# HyperArmBoard.net
KiCad netlist of a schematic drawn in EAGLE
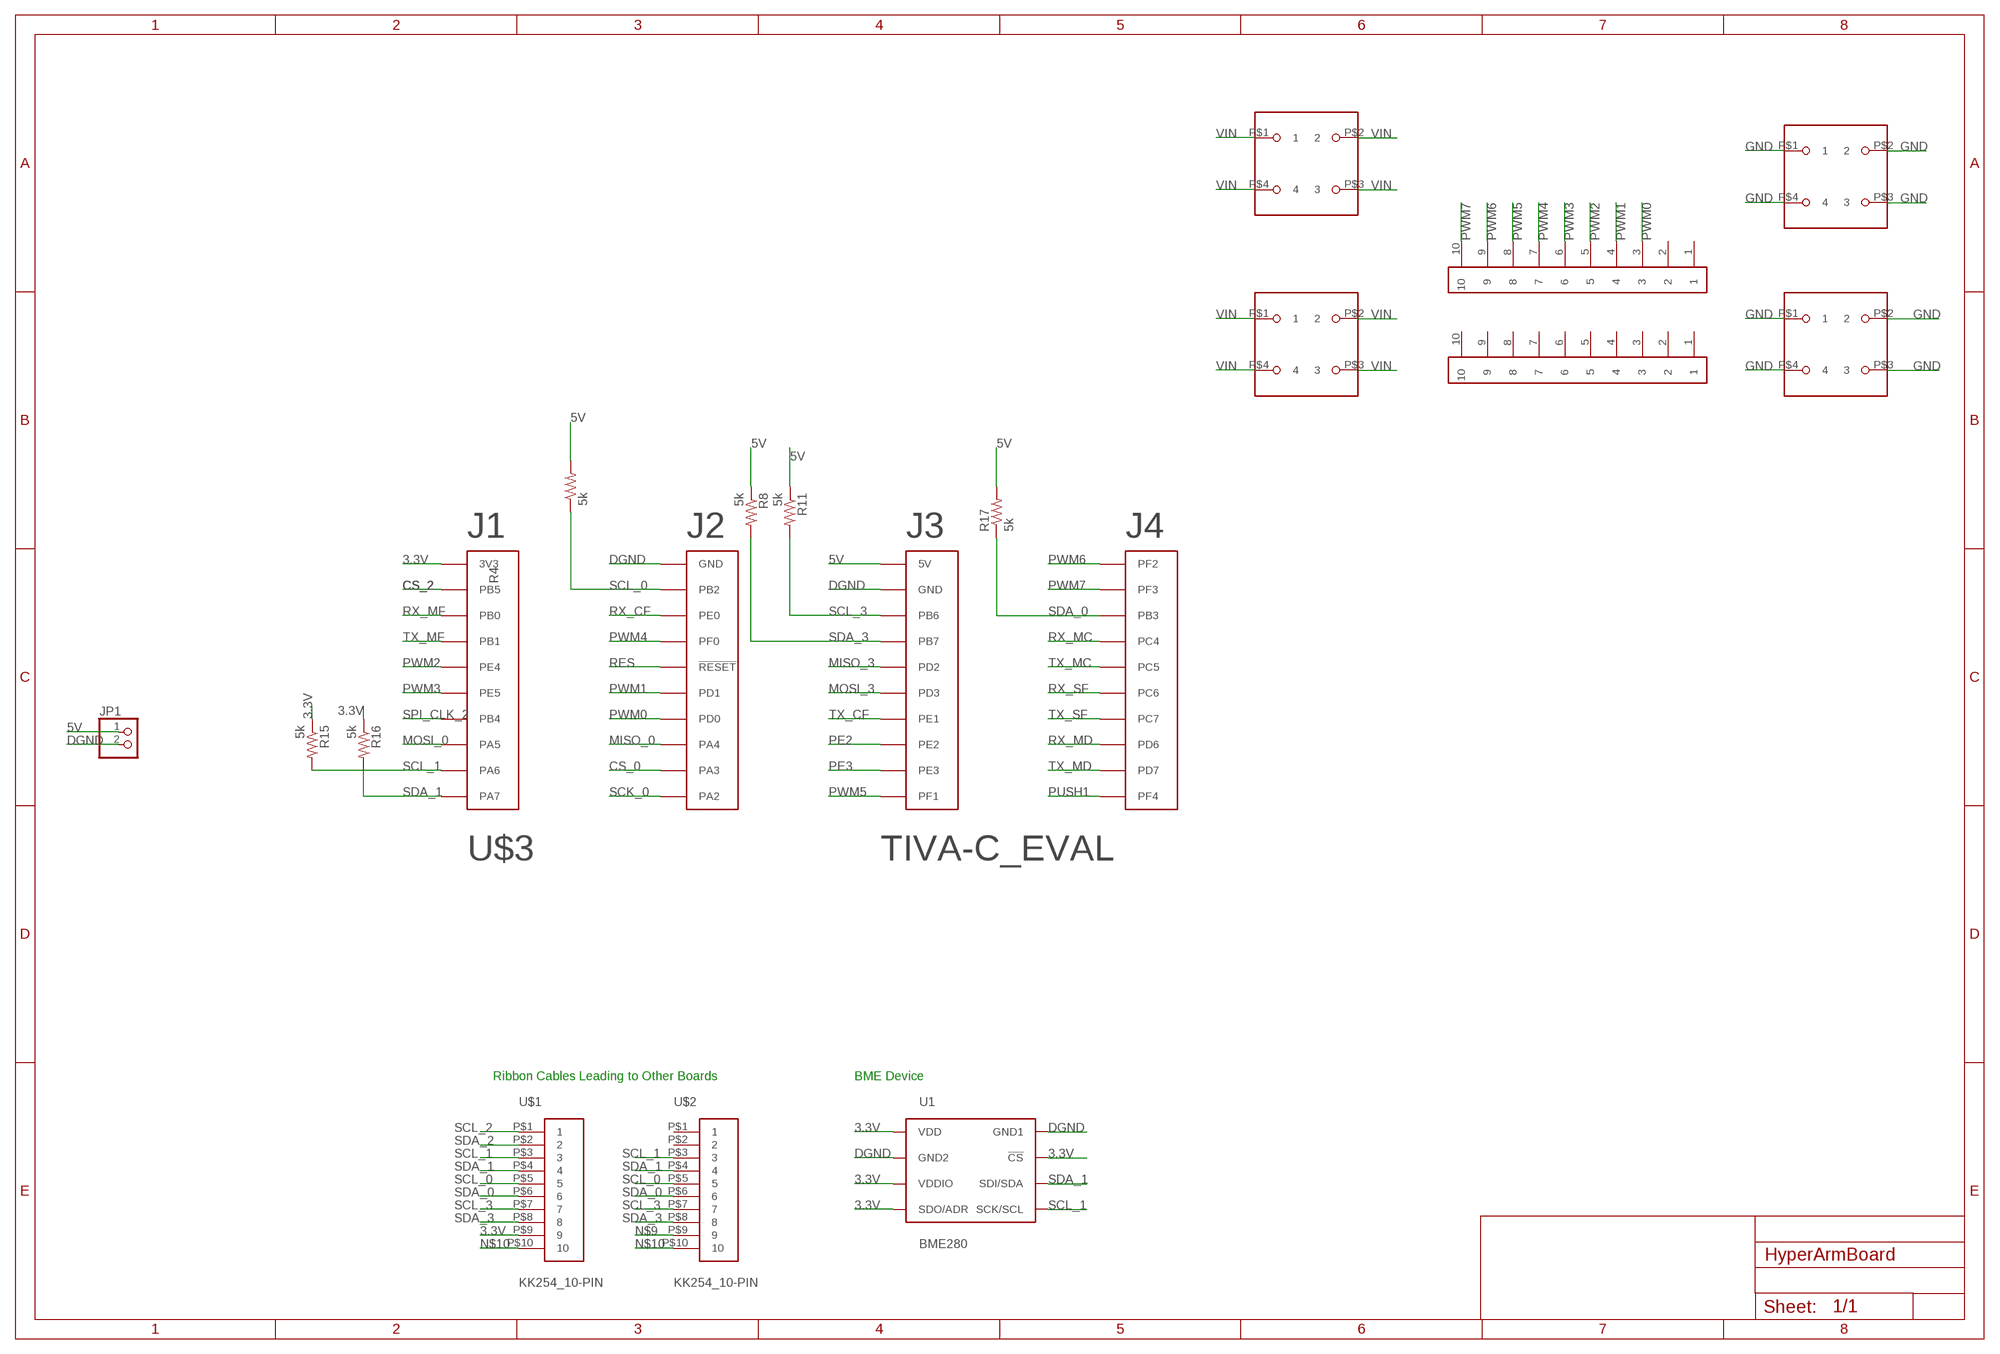
[diagram p0: schematic, sheet 1]

(export (version "E")
  (design (tool "Eeschema 10.0.6"))
  (components
    (comp (ref "JP1")
      (value "PINHD-1X2")
      (footprint "eagle-import:1X02")
      (libsource (lib "eagle-import") (part "PINHD-1X2"))
    )
    (comp (ref "R4")
      (value "5k")
      (footprint "eagle-import:R0805")
      (libsource (lib "eagle-import") (part "R-US_R0805"))
    )
    (comp (ref "R8")
      (value "5k")
      (footprint "eagle-import:R0805")
      (libsource (lib "eagle-import") (part "R-US_R0805"))
    )
    (comp (ref "R11")
      (value "5k")
      (footprint "eagle-import:R0805")
      (libsource (lib "eagle-import") (part "R-US_R0805"))
    )
    (comp (ref "R15")
      (value "5k")
      (footprint "eagle-import:R0805")
      (libsource (lib "eagle-import") (part "R-US_R0805"))
    )
    (comp (ref "R16")
      (value "5k")
      (footprint "eagle-import:R0805")
      (libsource (lib "eagle-import") (part "R-US_R0805"))
    )
    (comp (ref "R17")
      (value "5k")
      (footprint "eagle-import:R0805")
      (libsource (lib "eagle-import") (part "R-US_R0805"))
    )
    (comp (ref "U$1")
      (value "KK254_10-PIN")
      (footprint "eagle-import:KK254_10-PIN")
      (libsource (lib "eagle-import") (part "KK254_10-PIN"))
    )
    (comp (ref "U$2")
      (value "KK254_10-PIN")
      (footprint "eagle-import:KK254_10-PIN")
      (libsource (lib "eagle-import") (part "KK254_10-PIN"))
    )
    (comp (ref "U$3")
      (value "TIVA-C_EVAL")
      (footprint "eagle-import:TIVA-C_EVAL")
      (libsource (lib "eagle-import") (part "TIVA-C_EVAL"))
    )
    (comp (ref "U$4")
      (value "BCS-106-L-D-PE-BE")
      (footprint "eagle-import:4-PIN-BIGPOWER")
      (libsource (lib "eagle-import") (part "BCS-106-L-D-PE-BE"))
    )
    (comp (ref "U$5")
      (value "BCS-106-L-D-PE-BE")
      (footprint "eagle-import:4-PIN-BIGPOWER")
      (libsource (lib "eagle-import") (part "BCS-106-L-D-PE-BE"))
    )
    (comp (ref "U$6")
      (value "BCS-106-L-D-PE-BE")
      (footprint "eagle-import:4-PIN-BIGPOWER")
      (libsource (lib "eagle-import") (part "BCS-106-L-D-PE-BE"))
    )
    (comp (ref "U$7")
      (value "BCS-106-L-D-PE-BE")
      (footprint "eagle-import:4-PIN-BIGPOWER")
      (libsource (lib "eagle-import") (part "BCS-106-L-D-PE-BE"))
    )
    (comp (ref "U$10")
      (value "CONN-RECEPT-2MM-VERT-AU-10POS")
      (footprint "eagle-import:10-PIN-LILPWR")
      (libsource (lib "eagle-import") (part "CONN-RECEPT-2MM-VERT-AU-10POS"))
    )
    (comp (ref "U$11")
      (value "CONN-RECEPT-2MM-VERT-AU-10POS")
      (footprint "eagle-import:10-PIN-LILPWR")
      (libsource (lib "eagle-import") (part "CONN-RECEPT-2MM-VERT-AU-10POS"))
    )
    (comp (ref "U1")
      (value "BME280")
      (footprint "eagle-import:BME280_LGA")
      (libsource (lib "eagle-import") (part "BME280"))
    )
  )
  (nets
    (net (code "1") (name "/3.3V") (class "Default")
      (node (ref "R15") (pin "1") (pinfunction "1_1") (pintype "passive"))
      (node (ref "R16") (pin "1") (pinfunction "1_1") (pintype "passive"))
      (node (ref "U$1") (pin "P$9") (pinfunction "9_P$9") (pintype "bidirectional"))
      (node (ref "U$3") (pin "1-1") (pinfunction "3V3_1-1") (pintype "bidirectional"))
      (node (ref "U1") (pin "P$2") (pinfunction "~{CS}_P$2") (pintype "bidirectional"))
      (node (ref "U1") (pin "P$5") (pinfunction "SDO/ADR_P$5") (pintype "bidirectional"))
      (node (ref "U1") (pin "P$6") (pinfunction "VDDIO_P$6") (pintype "bidirectional"))
      (node (ref "U1") (pin "P$8") (pinfunction "VDD_P$8") (pintype "bidirectional"))
    )
    (net (code "2") (name "/5V") (class "Default")
      (node (ref "JP1") (pin "1") (pinfunction "1_1") (pintype "passive"))
      (node (ref "R11") (pin "1") (pinfunction "1_1") (pintype "passive"))
      (node (ref "R17") (pin "2") (pinfunction "2_2") (pintype "passive"))
      (node (ref "R4") (pin "2") (pinfunction "2_2") (pintype "passive"))
      (node (ref "R8") (pin "1") (pinfunction "1_1") (pintype "passive"))
      (node (ref "U$3") (pin "3-1") (pinfunction "5V_3-1") (pintype "bidirectional"))
    )
    (net (code "3") (name "/CS_0") (class "Default")
      (node (ref "U$3") (pin "2-9") (pinfunction "PA3_2-9") (pintype "bidirectional"))
    )
    (net (code "4") (name "/CS_2") (class "Default")
      (node (ref "U$3") (pin "1-2") (pinfunction "PB5_1-2") (pintype "bidirectional"))
    )
    (net (code "5") (name "/DGND") (class "Default")
      (node (ref "JP1") (pin "2") (pinfunction "2_2") (pintype "passive"))
      (node (ref "U$3") (pin "2-1") (pinfunction "GND_2-1") (pintype "bidirectional"))
      (node (ref "U$3") (pin "3-2") (pinfunction "GND_3-2") (pintype "bidirectional"))
      (node (ref "U1") (pin "P$1") (pinfunction "GND1_P$1") (pintype "bidirectional"))
      (node (ref "U1") (pin "P$7") (pinfunction "GND2_P$7") (pintype "bidirectional"))
    )
    (net (code "6") (name "/GND") (class "Default")
      (node (ref "U$6") (pin "P$1") (pinfunction "1_P$1") (pintype "bidirectional"))
      (node (ref "U$6") (pin "P$2") (pinfunction "2_P$2") (pintype "bidirectional"))
      (node (ref "U$6") (pin "P$3") (pinfunction "3_P$3") (pintype "bidirectional"))
      (node (ref "U$6") (pin "P$4") (pinfunction "4_P$4") (pintype "bidirectional"))
      (node (ref "U$7") (pin "P$1") (pinfunction "1_P$1") (pintype "bidirectional"))
      (node (ref "U$7") (pin "P$2") (pinfunction "2_P$2") (pintype "bidirectional"))
      (node (ref "U$7") (pin "P$3") (pinfunction "3_P$3") (pintype "bidirectional"))
      (node (ref "U$7") (pin "P$4") (pinfunction "4_P$4") (pintype "bidirectional"))
    )
    (net (code "7") (name "/MISO_0") (class "Default")
      (node (ref "U$3") (pin "2-8") (pinfunction "PA4_2-8") (pintype "bidirectional"))
    )
    (net (code "8") (name "/MISO_3") (class "Default")
      (node (ref "U$3") (pin "3-5") (pinfunction "PD2_3-5") (pintype "bidirectional"))
    )
    (net (code "9") (name "/MOSI_0") (class "Default")
      (node (ref "U$3") (pin "1-8") (pinfunction "PA5_1-8") (pintype "bidirectional"))
    )
    (net (code "10") (name "/MOSI_3") (class "Default")
      (node (ref "U$3") (pin "3-6") (pinfunction "PD3_3-6") (pintype "bidirectional"))
    )
    (net (code "11") (name "/N$9") (class "Default")
      (node (ref "U$2") (pin "P$9") (pinfunction "9_P$9") (pintype "bidirectional"))
    )
    (net (code "12") (name "/N$10") (class "Default")
      (node (ref "U$1") (pin "P$10") (pinfunction "10_P$10") (pintype "bidirectional"))
      (node (ref "U$2") (pin "P$10") (pinfunction "10_P$10") (pintype "bidirectional"))
    )
    (net (code "13") (name "/PE2") (class "Default")
      (node (ref "U$3") (pin "3-8") (pinfunction "PE2_3-8") (pintype "bidirectional"))
    )
    (net (code "14") (name "/PE3") (class "Default")
      (node (ref "U$3") (pin "3-9") (pinfunction "PE3_3-9") (pintype "bidirectional"))
    )
    (net (code "15") (name "/PUSH1") (class "Default")
      (node (ref "U$3") (pin "4-10") (pinfunction "PF4_4-10") (pintype "bidirectional"))
    )
    (net (code "16") (name "/PWM0") (class "Default")
      (node (ref "U$10") (pin "3") (pinfunction "3_3") (pintype "bidirectional"))
      (node (ref "U$3") (pin "2-7") (pinfunction "PD0_2-7") (pintype "bidirectional"))
    )
    (net (code "17") (name "/PWM1") (class "Default")
      (node (ref "U$10") (pin "4") (pinfunction "4_4") (pintype "bidirectional"))
      (node (ref "U$3") (pin "2-6") (pinfunction "PD1_2-6") (pintype "bidirectional"))
    )
    (net (code "18") (name "/PWM2") (class "Default")
      (node (ref "U$10") (pin "5") (pinfunction "5_5") (pintype "bidirectional"))
      (node (ref "U$3") (pin "1-5") (pinfunction "PE4_1-5") (pintype "bidirectional"))
    )
    (net (code "19") (name "/PWM3") (class "Default")
      (node (ref "U$10") (pin "6") (pinfunction "6_6") (pintype "bidirectional"))
      (node (ref "U$3") (pin "1-6") (pinfunction "PE5_1-6") (pintype "bidirectional"))
    )
    (net (code "20") (name "/PWM4") (class "Default")
      (node (ref "U$10") (pin "7") (pinfunction "7_7") (pintype "bidirectional"))
      (node (ref "U$3") (pin "2-4") (pinfunction "PF0_2-4") (pintype "bidirectional"))
    )
    (net (code "21") (name "/PWM5") (class "Default")
      (node (ref "U$10") (pin "8") (pinfunction "8_8") (pintype "bidirectional"))
      (node (ref "U$3") (pin "3-10") (pinfunction "PF1_3-10") (pintype "bidirectional"))
    )
    (net (code "22") (name "/PWM6") (class "Default")
      (node (ref "U$10") (pin "9") (pinfunction "9_9") (pintype "bidirectional"))
      (node (ref "U$3") (pin "4-1") (pinfunction "PF2_4-1") (pintype "bidirectional"))
    )
    (net (code "23") (name "/PWM7") (class "Default")
      (node (ref "U$10") (pin "10") (pinfunction "10_10") (pintype "bidirectional"))
      (node (ref "U$3") (pin "4-2") (pinfunction "PF3_4-2") (pintype "bidirectional"))
    )
    (net (code "24") (name "/RES") (class "Default")
      (node (ref "U$3") (pin "2-5") (pinfunction "~{RESET}_2-5") (pintype "bidirectional"))
    )
    (net (code "25") (name "/RX_CF") (class "Default")
      (node (ref "U$3") (pin "2-3") (pinfunction "PE0_2-3") (pintype "bidirectional"))
    )
    (net (code "26") (name "/RX_MC") (class "Default")
      (node (ref "U$3") (pin "4-4") (pinfunction "PC4_4-4") (pintype "bidirectional"))
    )
    (net (code "27") (name "/RX_MD") (class "Default")
      (node (ref "U$3") (pin "4-8") (pinfunction "PD6_4-8") (pintype "bidirectional"))
    )
    (net (code "28") (name "/RX_MF") (class "Default")
      (node (ref "U$3") (pin "1-3") (pinfunction "PB0_1-3") (pintype "bidirectional"))
    )
    (net (code "29") (name "/RX_SF") (class "Default")
      (node (ref "U$3") (pin "4-6") (pinfunction "PC6_4-6") (pintype "bidirectional"))
    )
    (net (code "30") (name "/SCK_0") (class "Default")
      (node (ref "U$3") (pin "2-10") (pinfunction "PA2_2-10") (pintype "bidirectional"))
    )
    (net (code "31") (name "/SCL_0") (class "Default")
      (node (ref "R4") (pin "1") (pinfunction "1_1") (pintype "passive"))
      (node (ref "U$1") (pin "P$5") (pinfunction "5_P$5") (pintype "bidirectional"))
      (node (ref "U$2") (pin "P$5") (pinfunction "5_P$5") (pintype "bidirectional"))
      (node (ref "U$3") (pin "2-2") (pinfunction "PB2_2-2") (pintype "bidirectional"))
    )
    (net (code "32") (name "/SCL_1") (class "Default")
      (node (ref "R15") (pin "2") (pinfunction "2_2") (pintype "passive"))
      (node (ref "U$1") (pin "P$3") (pinfunction "3_P$3") (pintype "bidirectional"))
      (node (ref "U$2") (pin "P$3") (pinfunction "3_P$3") (pintype "bidirectional"))
      (node (ref "U$3") (pin "1-9") (pinfunction "PA6_1-9") (pintype "bidirectional"))
      (node (ref "U1") (pin "P$4") (pinfunction "SCK/SCL_P$4") (pintype "bidirectional"))
    )
    (net (code "33") (name "/SCL_2") (class "Default")
      (node (ref "U$1") (pin "P$1") (pinfunction "1_P$1") (pintype "bidirectional"))
    )
    (net (code "34") (name "/SCL_3") (class "Default")
      (node (ref "R11") (pin "2") (pinfunction "2_2") (pintype "passive"))
      (node (ref "U$1") (pin "P$7") (pinfunction "7_P$7") (pintype "bidirectional"))
      (node (ref "U$2") (pin "P$7") (pinfunction "7_P$7") (pintype "bidirectional"))
      (node (ref "U$3") (pin "3-3") (pinfunction "PB6_3-3") (pintype "bidirectional"))
    )
    (net (code "35") (name "/SDA_0") (class "Default")
      (node (ref "R17") (pin "1") (pinfunction "1_1") (pintype "passive"))
      (node (ref "U$1") (pin "P$6") (pinfunction "6_P$6") (pintype "bidirectional"))
      (node (ref "U$2") (pin "P$6") (pinfunction "6_P$6") (pintype "bidirectional"))
      (node (ref "U$3") (pin "4-3") (pinfunction "PB3_4-3") (pintype "bidirectional"))
    )
    (net (code "36") (name "/SDA_1") (class "Default")
      (node (ref "R16") (pin "2") (pinfunction "2_2") (pintype "passive"))
      (node (ref "U$1") (pin "P$4") (pinfunction "4_P$4") (pintype "bidirectional"))
      (node (ref "U$2") (pin "P$4") (pinfunction "4_P$4") (pintype "bidirectional"))
      (node (ref "U$3") (pin "1-10") (pinfunction "PA7_1-10") (pintype "bidirectional"))
      (node (ref "U1") (pin "P$3") (pinfunction "SDI/SDA_P$3") (pintype "bidirectional"))
    )
    (net (code "37") (name "/SDA_2") (class "Default")
      (node (ref "U$1") (pin "P$2") (pinfunction "2_P$2") (pintype "bidirectional"))
    )
    (net (code "38") (name "/SDA_3") (class "Default")
      (node (ref "R8") (pin "2") (pinfunction "2_2") (pintype "passive"))
      (node (ref "U$1") (pin "P$8") (pinfunction "8_P$8") (pintype "bidirectional"))
      (node (ref "U$2") (pin "P$8") (pinfunction "8_P$8") (pintype "bidirectional"))
      (node (ref "U$3") (pin "3-4") (pinfunction "PB7_3-4") (pintype "bidirectional"))
    )
    (net (code "39") (name "/SPI_CLK_2") (class "Default")
      (node (ref "U$3") (pin "1-7") (pinfunction "PB4_1-7") (pintype "bidirectional"))
    )
    (net (code "40") (name "/TX_CF") (class "Default")
      (node (ref "U$3") (pin "3-7") (pinfunction "PE1_3-7") (pintype "bidirectional"))
    )
    (net (code "41") (name "/TX_MC") (class "Default")
      (node (ref "U$3") (pin "4-5") (pinfunction "PC5_4-5") (pintype "bidirectional"))
    )
    (net (code "42") (name "/TX_MD") (class "Default")
      (node (ref "U$3") (pin "4-9") (pinfunction "PD7_4-9") (pintype "bidirectional"))
    )
    (net (code "43") (name "/TX_MF") (class "Default")
      (node (ref "U$3") (pin "1-4") (pinfunction "PB1_1-4") (pintype "bidirectional"))
    )
    (net (code "44") (name "/TX_SF") (class "Default")
      (node (ref "U$3") (pin "4-7") (pinfunction "PC7_4-7") (pintype "bidirectional"))
    )
    (net (code "45") (name "/VIN") (class "Default")
      (node (ref "U$4") (pin "P$1") (pinfunction "1_P$1") (pintype "bidirectional"))
      (node (ref "U$4") (pin "P$2") (pinfunction "2_P$2") (pintype "bidirectional"))
      (node (ref "U$4") (pin "P$3") (pinfunction "3_P$3") (pintype "bidirectional"))
      (node (ref "U$4") (pin "P$4") (pinfunction "4_P$4") (pintype "bidirectional"))
      (node (ref "U$5") (pin "P$1") (pinfunction "1_P$1") (pintype "bidirectional"))
      (node (ref "U$5") (pin "P$2") (pinfunction "2_P$2") (pintype "bidirectional"))
      (node (ref "U$5") (pin "P$3") (pinfunction "3_P$3") (pintype "bidirectional"))
      (node (ref "U$5") (pin "P$4") (pinfunction "4_P$4") (pintype "bidirectional"))
    )
    (net (code "46") (name "unconnected-(U$2-1-PadP$1)") (class "Default")
      (node (ref "U$2") (pin "P$1") (pinfunction "1_P$1") (pintype "bidirectional"))
    )
    (net (code "47") (name "unconnected-(U$2-2-PadP$2)") (class "Default")
      (node (ref "U$2") (pin "P$2") (pinfunction "2_P$2") (pintype "bidirectional"))
    )
    (net (code "48") (name "unconnected-(U$10-Pad1)") (class "Default")
      (node (ref "U$10") (pin "1") (pinfunction "1_1") (pintype "bidirectional"))
    )
    (net (code "49") (name "unconnected-(U$10-Pad2)") (class "Default")
      (node (ref "U$10") (pin "2") (pinfunction "2_2") (pintype "bidirectional"))
    )
    (net (code "50") (name "unconnected-(U$11-Pad1)") (class "Default")
      (node (ref "U$11") (pin "1") (pinfunction "1_1") (pintype "bidirectional"))
    )
    (net (code "51") (name "unconnected-(U$11-Pad2)") (class "Default")
      (node (ref "U$11") (pin "2") (pinfunction "2_2") (pintype "bidirectional"))
    )
    (net (code "52") (name "unconnected-(U$11-Pad3)") (class "Default")
      (node (ref "U$11") (pin "3") (pinfunction "3_3") (pintype "bidirectional"))
    )
    (net (code "53") (name "unconnected-(U$11-Pad4)") (class "Default")
      (node (ref "U$11") (pin "4") (pinfunction "4_4") (pintype "bidirectional"))
    )
    (net (code "54") (name "unconnected-(U$11-Pad5)") (class "Default")
      (node (ref "U$11") (pin "5") (pinfunction "5_5") (pintype "bidirectional"))
    )
    (net (code "55") (name "unconnected-(U$11-Pad6)") (class "Default")
      (node (ref "U$11") (pin "6") (pinfunction "6_6") (pintype "bidirectional"))
    )
    (net (code "56") (name "unconnected-(U$11-Pad7)") (class "Default")
      (node (ref "U$11") (pin "7") (pinfunction "7_7") (pintype "bidirectional"))
    )
    (net (code "57") (name "unconnected-(U$11-Pad8)") (class "Default")
      (node (ref "U$11") (pin "8") (pinfunction "8_8") (pintype "bidirectional"))
    )
    (net (code "58") (name "unconnected-(U$11-Pad9)") (class "Default")
      (node (ref "U$11") (pin "9") (pinfunction "9_9") (pintype "bidirectional"))
    )
    (net (code "59") (name "unconnected-(U$11-Pad10)") (class "Default")
      (node (ref "U$11") (pin "10") (pinfunction "10_10") (pintype "bidirectional"))
    )
  )
)
